# IN-00.net
KiCad netlist of a schematic drawn in EAGLE
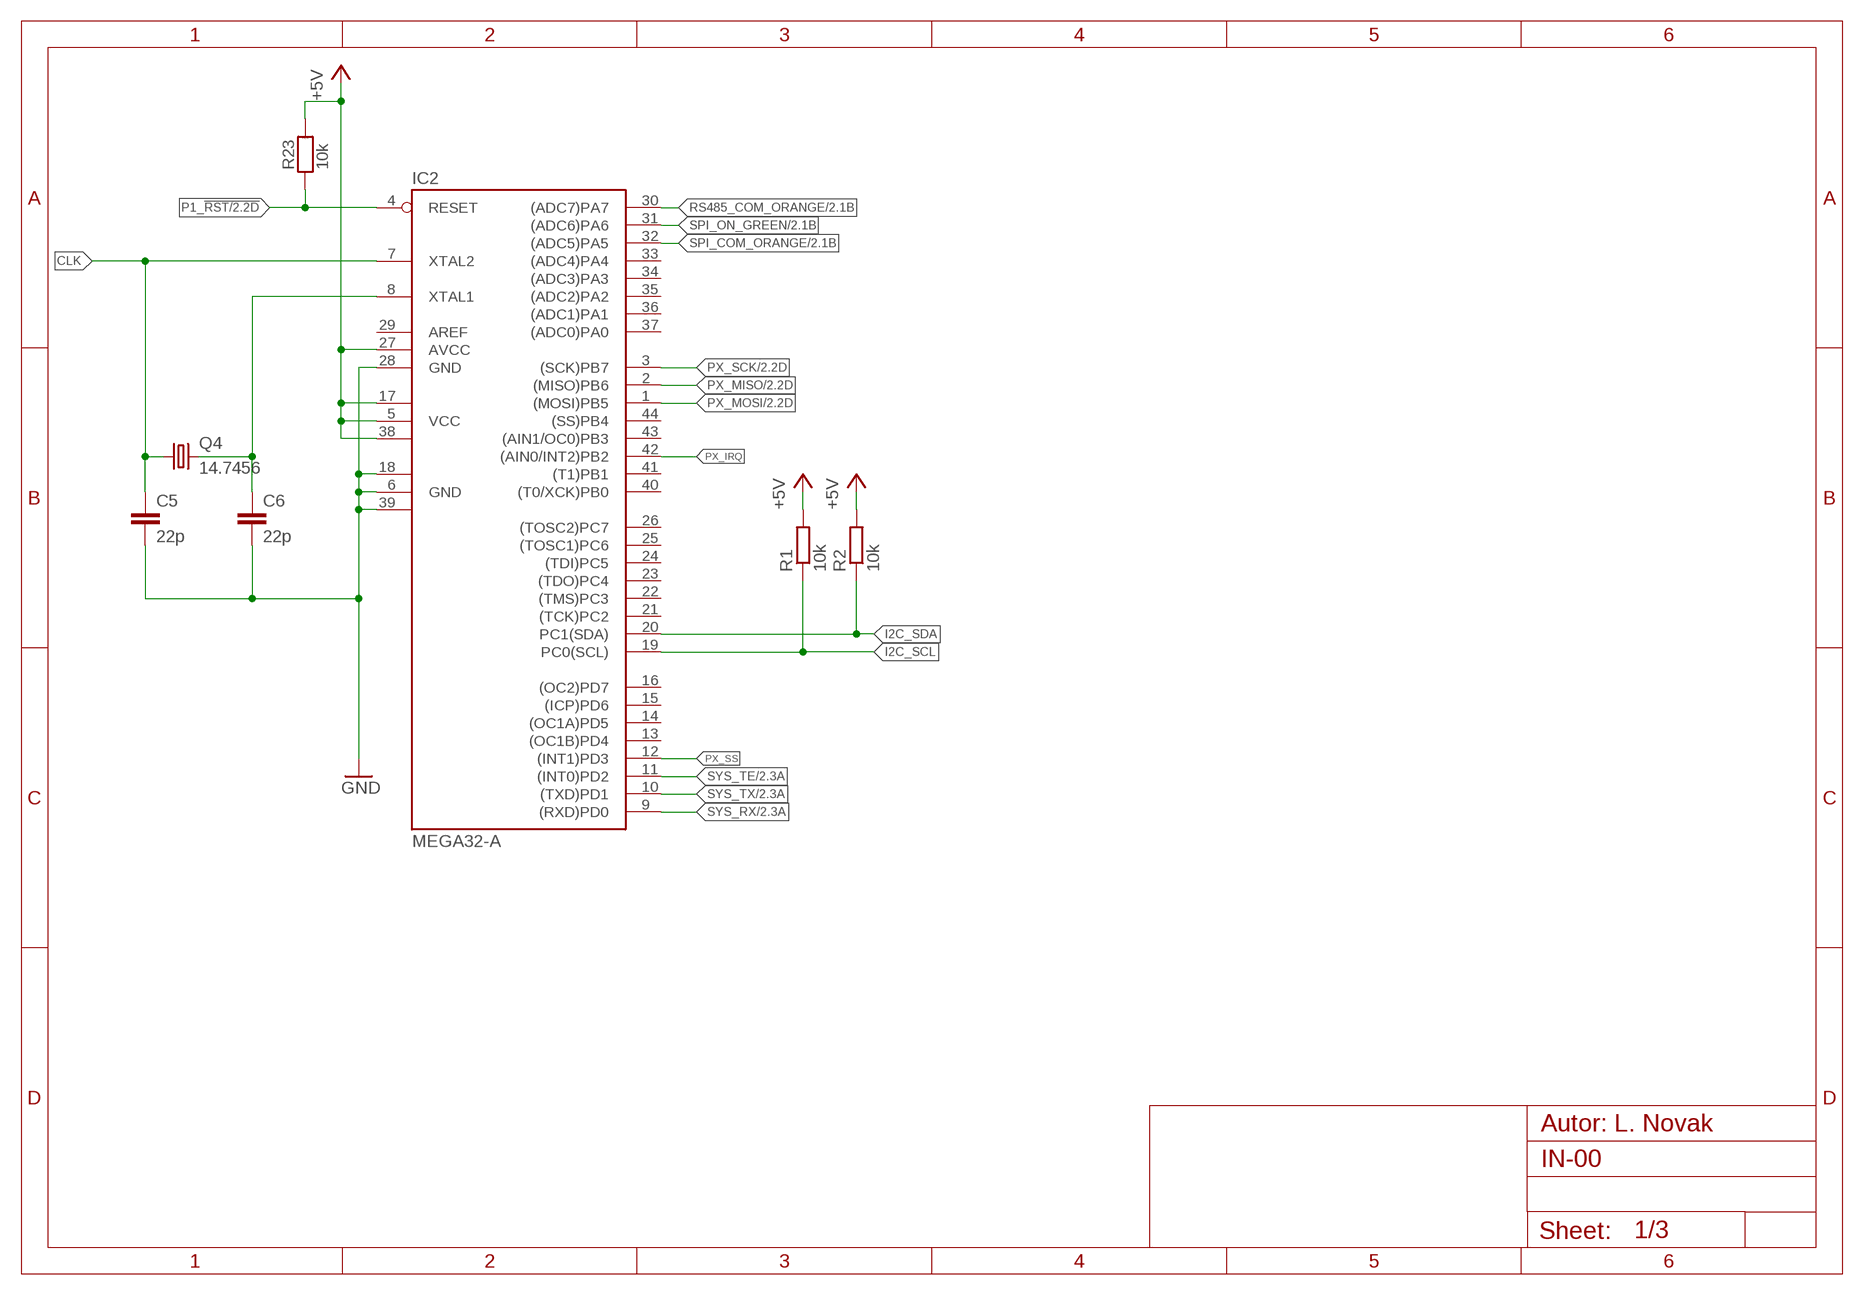
[diagram p0: schematic, sheet 1]
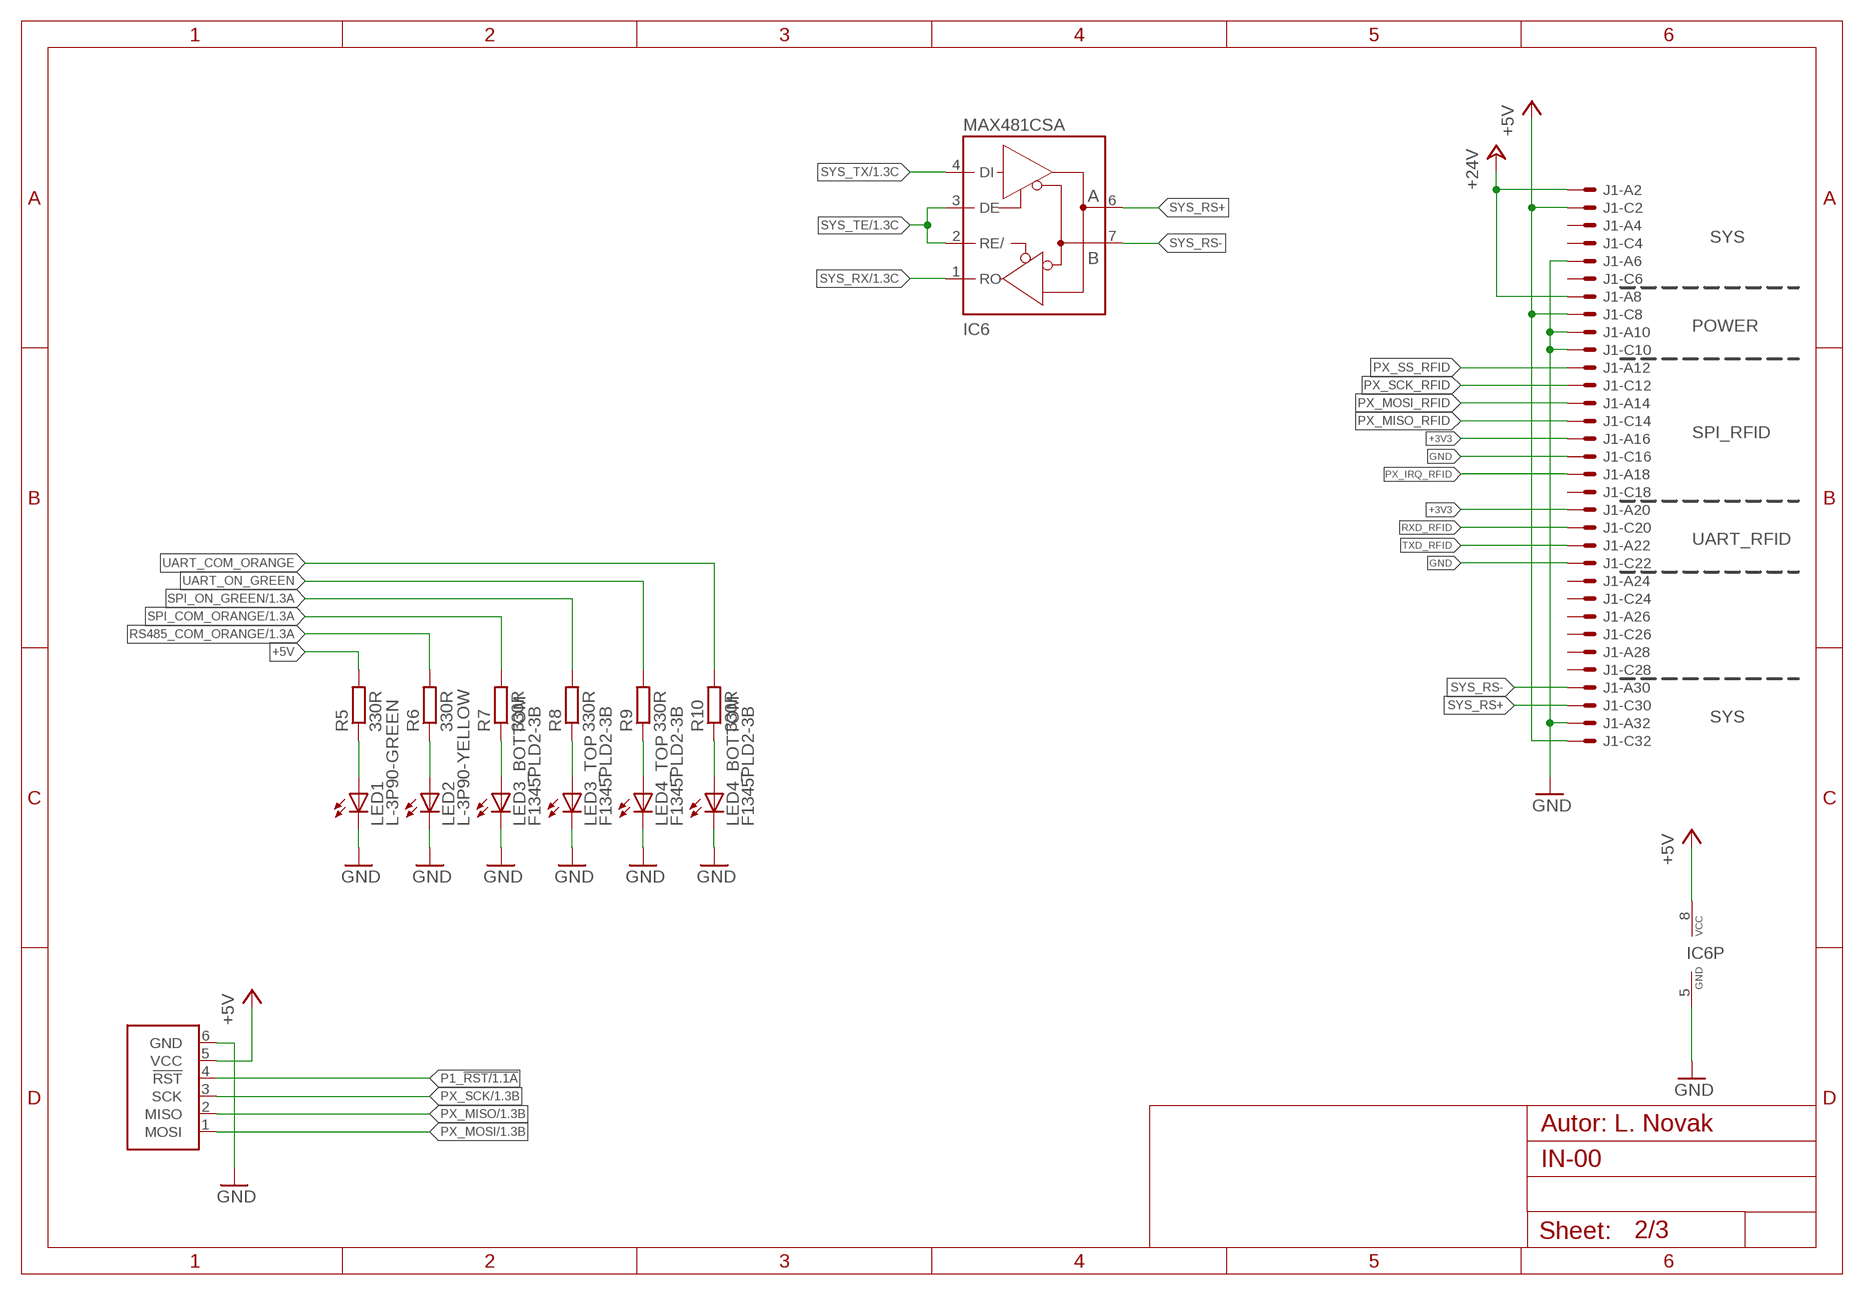
[diagram p1: schematic, sheet 2]
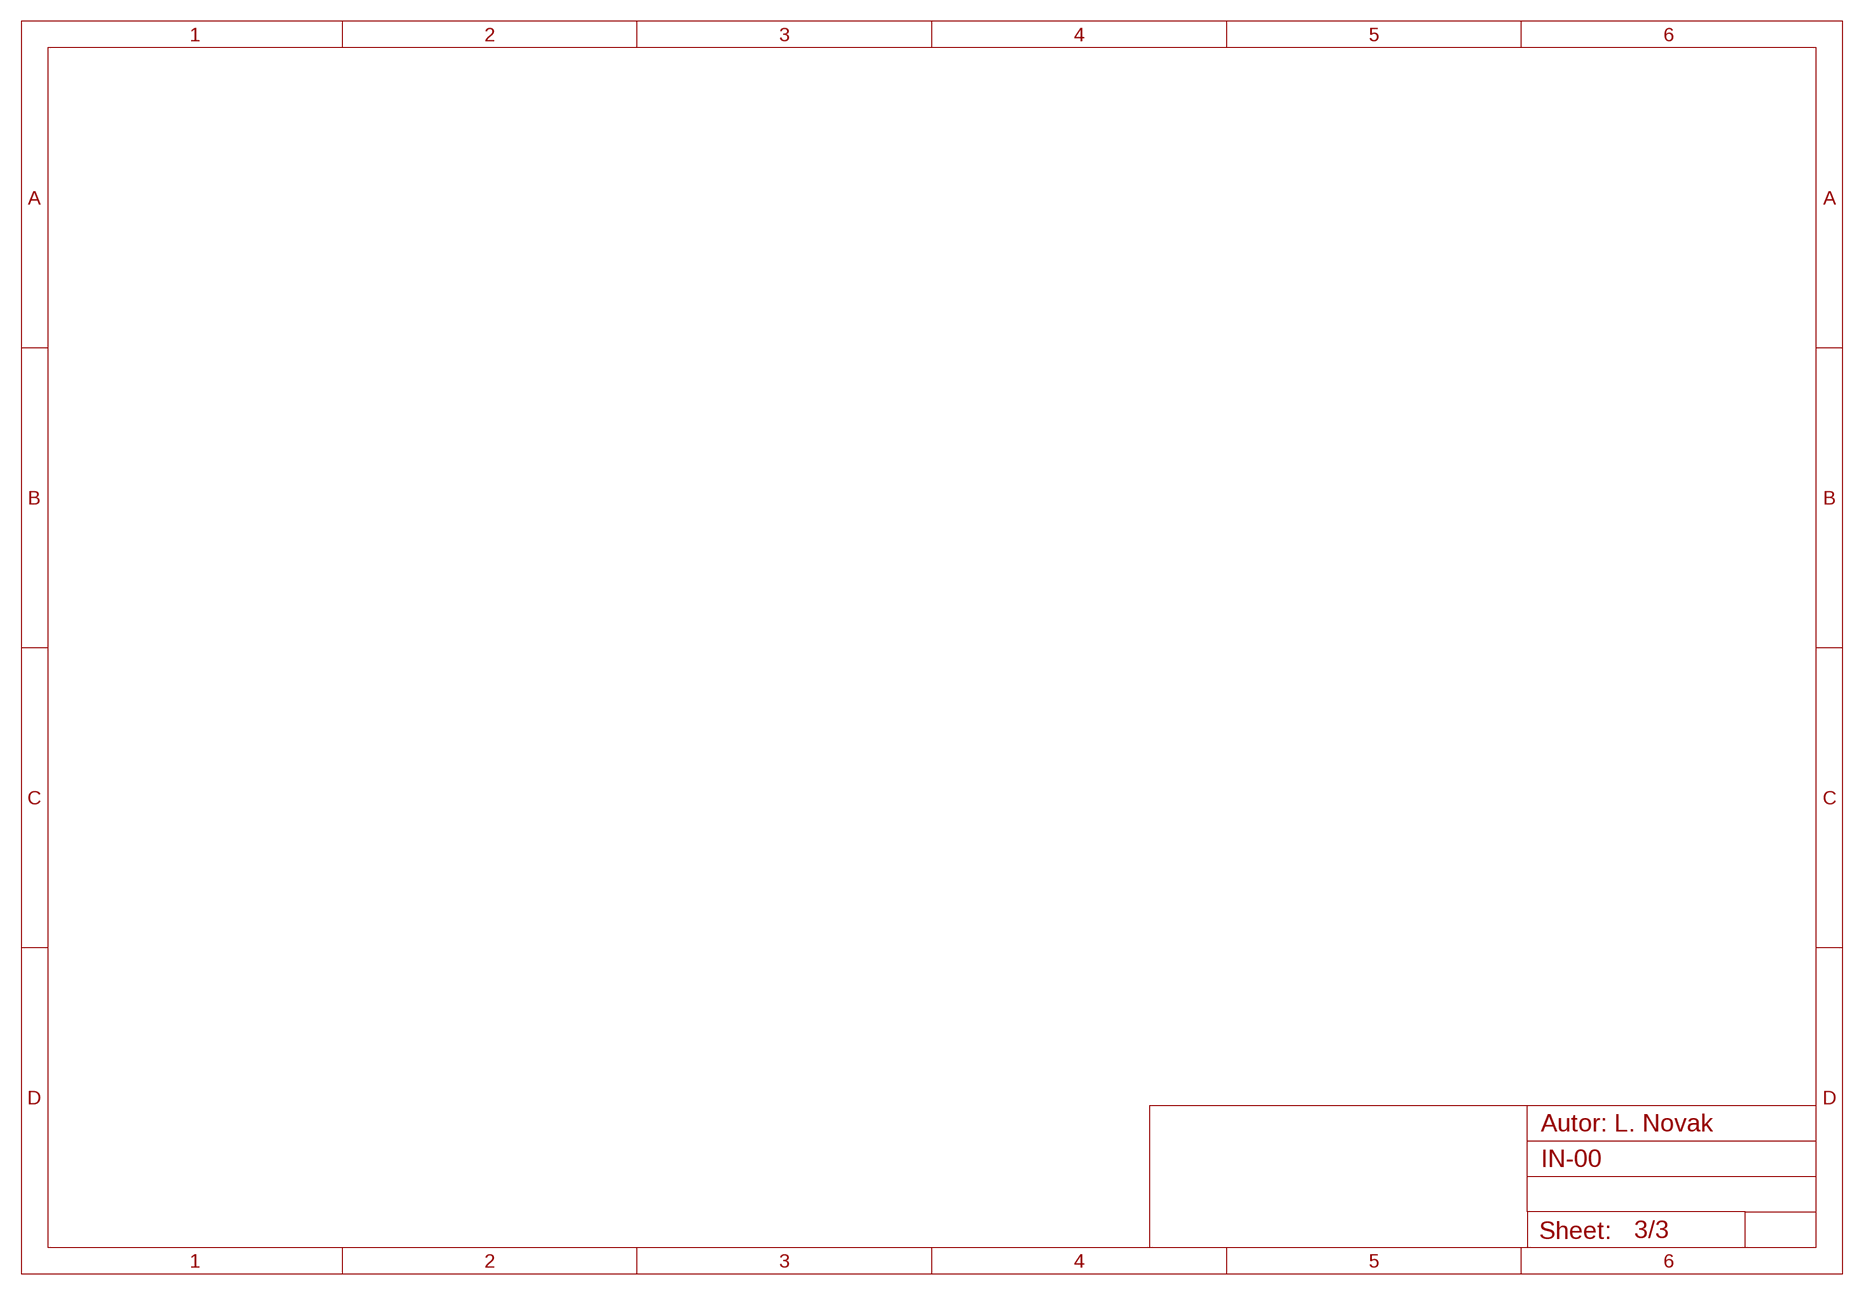
[diagram p2: schematic, sheet 3]

(export (version "E")
  (design (tool "Eeschema 10.0.6"))
  (components
    (comp (ref "IC6")
      (value "MAX481CSA")
      (footprint "eagle-import:SO08")
      (libsource (lib "eagle-import") (part "MAX481CSA"))
    )
    (comp (ref "J1")
      (value "VG32SP")
      (footprint "eagle-import:VG32P")
      (libsource (lib "eagle-import") (part "VG32SP"))
    )
    (comp (ref "LED1")
      (value "L-3P90-GREEN")
      (footprint "eagle-import:L-3P90")
      (libsource (lib "eagle-import") (part "L-3P90-GREEN"))
    )
    (comp (ref "LED2")
      (value "L-3P90-YELLOW")
      (footprint "eagle-import:L-3P90")
      (libsource (lib "eagle-import") (part "L-3P90-YELLOW"))
    )
    (comp (ref "LED3")
      (value "F1345PLD2-3B")
      (footprint "eagle-import:F1345PLD2-3B")
      (libsource (lib "eagle-import") (part "F1345PLD2-3B"))
    )
    (comp (ref "LED4")
      (value "F1345PLD2-3B")
      (footprint "eagle-import:F1345PLD2-3B")
      (libsource (lib "eagle-import") (part "F1345PLD2-3B"))
    )
    (comp (ref "R5")
      (value "330R")
      (footprint "eagle-import:R1206")
      (libsource (lib "eagle-import") (part "R-EU_R1206"))
    )
    (comp (ref "R6")
      (value "330R")
      (footprint "eagle-import:R1206")
      (libsource (lib "eagle-import") (part "R-EU_R1206"))
    )
    (comp (ref "R7")
      (value "330R")
      (footprint "eagle-import:R1206")
      (libsource (lib "eagle-import") (part "R-EU_R1206"))
    )
    (comp (ref "R8")
      (value "330R")
      (footprint "eagle-import:R1206")
      (libsource (lib "eagle-import") (part "R-EU_R1206"))
    )
    (comp (ref "R9")
      (value "330R")
      (footprint "eagle-import:R1206")
      (libsource (lib "eagle-import") (part "R-EU_R1206"))
    )
    (comp (ref "R10")
      (value "330R")
      (footprint "eagle-import:R1206")
      (libsource (lib "eagle-import") (part "R-EU_R1206"))
    )
    (comp (ref "U1")
      (value "ATPROG-V")
      (footprint "eagle-import:6410-06")
      (libsource (lib "eagle-import") (part "ATPROG-V"))
    )
    (comp (ref "C5")
      (value "22p")
      (footprint "eagle-import:C0805")
      (libsource (lib "eagle-import") (part "C-EUC0805"))
    )
    (comp (ref "C6")
      (value "22p")
      (footprint "eagle-import:C0805")
      (libsource (lib "eagle-import") (part "C-EUC0805"))
    )
    (comp (ref "IC2")
      (value "MEGA32-A")
      (footprint "eagle-import:TQFP44")
      (fields (field (name "MPN") "ATMEGA32-16AU"))
      (libsource (lib "eagle-import") (part "MEGA32-A"))
    )
    (comp (ref "Q4")
      (value "14.7456")
      (footprint "eagle-import:HC49U70")
      (libsource (lib "eagle-import") (part "XTAL"))
    )
    (comp (ref "R1")
      (value "10k")
      (footprint "eagle-import:R1206")
      (libsource (lib "eagle-import") (part "R-EU_R1206"))
    )
    (comp (ref "R2")
      (value "10k")
      (footprint "eagle-import:R1206")
      (libsource (lib "eagle-import") (part "R-EU_R1206"))
    )
    (comp (ref "R23")
      (value "10k")
      (footprint "eagle-import:1206")
      (libsource (lib "eagle-import") (part "R_1206"))
    )
  )
  (nets
    (net (code "1") (name "+3V3") (class "Default")
      (node (ref "J1") (pin "A16") (pinfunction "MS_A16") (pintype "passive"))
      (node (ref "J1") (pin "A20") (pinfunction "MS_A20") (pintype "passive"))
    )
    (net (code "2") (name "+5V") (class "Default")
      (node (ref "IC2") (pin "17") (pinfunction "VCC1_17") (pintype "power_in"))
      (node (ref "IC2") (pin "27") (pinfunction "AVCC_27") (pintype "power_in"))
      (node (ref "IC2") (pin "38") (pinfunction "VCC2_38") (pintype "power_in"))
      (node (ref "IC2") (pin "5") (pinfunction "VCC_5") (pintype "power_in"))
      (node (ref "IC6") (pin "8") (pinfunction "VCC_8") (pintype "power_in"))
      (node (ref "J1") (pin "C2") (pinfunction "MS_C2") (pintype "passive"))
      (node (ref "J1") (pin "C32") (pinfunction "MSV_C32") (pintype "passive"))
      (node (ref "J1") (pin "C8") (pinfunction "MS_C8") (pintype "passive"))
      (node (ref "R1") (pin "2") (pinfunction "2_2") (pintype "passive"))
      (node (ref "R2") (pin "2") (pinfunction "2_2") (pintype "passive"))
      (node (ref "R23") (pin "2") (pinfunction "2_2") (pintype "passive"))
      (node (ref "R5") (pin "2") (pinfunction "2_2") (pintype "passive"))
      (node (ref "U1") (pin "5") (pinfunction "VCC_5") (pintype "power_in"))
    )
    (net (code "3") (name "+24V") (class "Default")
      (node (ref "J1") (pin "A2") (pinfunction "MS_A2") (pintype "passive"))
      (node (ref "J1") (pin "A8") (pinfunction "MS_A8") (pintype "passive"))
    )
    (net (code "4") (name "CLK") (class "Default")
      (node (ref "C5") (pin "1") (pinfunction "1_1") (pintype "passive"))
      (node (ref "IC2") (pin "7") (pinfunction "XTAL2_7") (pintype "bidirectional"))
      (node (ref "Q4") (pin "1") (pinfunction "1_1") (pintype "passive"))
    )
    (net (code "5") (name "GND") (class "Default")
      (node (ref "C5") (pin "2") (pinfunction "2_2") (pintype "passive"))
      (node (ref "C6") (pin "2") (pinfunction "2_2") (pintype "passive"))
      (node (ref "IC2") (pin "18") (pinfunction "GND1_18") (pintype "power_in"))
      (node (ref "IC2") (pin "28") (pinfunction "GND_28") (pintype "power_in"))
      (node (ref "IC2") (pin "39") (pinfunction "GND2_39") (pintype "power_in"))
      (node (ref "IC2") (pin "6") (pinfunction "GND_6") (pintype "power_in"))
      (node (ref "IC6") (pin "5") (pinfunction "GND_5") (pintype "power_in"))
      (node (ref "J1") (pin "A10") (pinfunction "MS_A10") (pintype "passive"))
      (node (ref "J1") (pin "A32") (pinfunction "MS_A32") (pintype "passive"))
      (node (ref "J1") (pin "A6") (pinfunction "MS_A6") (pintype "passive"))
      (node (ref "J1") (pin "C10") (pinfunction "MS_C10") (pintype "passive"))
      (node (ref "J1") (pin "C16") (pinfunction "MS_C16") (pintype "passive"))
      (node (ref "J1") (pin "C22") (pinfunction "MS_C22") (pintype "passive"))
      (node (ref "LED1") (pin "K") (pinfunction "C_K") (pintype "passive"))
      (node (ref "LED2") (pin "K") (pinfunction "C_K") (pintype "passive"))
      (node (ref "LED3") (pin "1K") (pinfunction "C_1K") (pintype "passive"))
      (node (ref "LED3") (pin "2K") (pinfunction "C_2K") (pintype "passive"))
      (node (ref "LED4") (pin "1K") (pinfunction "C_1K") (pintype "passive"))
      (node (ref "LED4") (pin "2K") (pinfunction "C_2K") (pintype "passive"))
      (node (ref "U1") (pin "6") (pinfunction "GND_6") (pintype "power_in"))
    )
    (net (code "6") (name "I2C_SCL") (class "Default")
      (node (ref "IC2") (pin "19") (pinfunction "PC0(SCL)_19") (pintype "bidirectional"))
      (node (ref "R1") (pin "1") (pinfunction "1_1") (pintype "passive"))
    )
    (net (code "7") (name "I2C_SDA") (class "Default")
      (node (ref "IC2") (pin "20") (pinfunction "PC1(SDA)_20") (pintype "bidirectional"))
      (node (ref "R2") (pin "1") (pinfunction "1_1") (pintype "passive"))
    )
    (net (code "8") (name "Net-(IC2-XTAL1)") (class "Default")
      (node (ref "C6") (pin "1") (pinfunction "1_1") (pintype "passive"))
      (node (ref "IC2") (pin "8") (pinfunction "XTAL1_8") (pintype "bidirectional"))
      (node (ref "Q4") (pin "2") (pinfunction "2_2") (pintype "passive"))
    )
    (net (code "9") (name "Net-(LED1-PadA)") (class "Default")
      (node (ref "LED1") (pin "A") (pinfunction "A_A") (pintype "passive"))
      (node (ref "R5") (pin "1") (pinfunction "1_1") (pintype "passive"))
    )
    (net (code "10") (name "Net-(LED2-PadA)") (class "Default")
      (node (ref "LED2") (pin "A") (pinfunction "A_A") (pintype "passive"))
      (node (ref "R6") (pin "1") (pinfunction "1_1") (pintype "passive"))
    )
    (net (code "11") (name "Net-(LED3A-A)") (class "Default")
      (node (ref "LED3") (pin "1A") (pinfunction "A_1A") (pintype "passive"))
      (node (ref "R7") (pin "1") (pinfunction "1_1") (pintype "passive"))
    )
    (net (code "12") (name "Net-(LED3B-A)") (class "Default")
      (node (ref "LED3") (pin "2A") (pinfunction "A_2A") (pintype "passive"))
      (node (ref "R8") (pin "1") (pinfunction "1_1") (pintype "passive"))
    )
    (net (code "13") (name "Net-(LED4A-A)") (class "Default")
      (node (ref "LED4") (pin "1A") (pinfunction "A_1A") (pintype "passive"))
      (node (ref "R10") (pin "1") (pinfunction "1_1") (pintype "passive"))
    )
    (net (code "14") (name "Net-(LED4B-A)") (class "Default")
      (node (ref "LED4") (pin "2A") (pinfunction "A_2A") (pintype "passive"))
      (node (ref "R9") (pin "1") (pinfunction "1_1") (pintype "passive"))
    )
    (net (code "15") (name "P1_~{RST}") (class "Default")
      (node (ref "IC2") (pin "4") (pinfunction "RESET_4") (pintype "input"))
      (node (ref "R23") (pin "1") (pinfunction "1_1") (pintype "passive"))
      (node (ref "U1") (pin "4") (pinfunction "~{RST}_4") (pintype "input"))
    )
    (net (code "16") (name "PX_IRQ") (class "Default")
      (node (ref "IC2") (pin "42") (pinfunction "(AIN0/INT2)PB2_42") (pintype "bidirectional"))
    )
    (net (code "17") (name "PX_IRQ_RFID") (class "Default")
      (node (ref "J1") (pin "A18") (pinfunction "MS_A18") (pintype "passive"))
    )
    (net (code "18") (name "PX_MISO") (class "Default")
      (node (ref "IC2") (pin "2") (pinfunction "(MISO)PB6_2") (pintype "bidirectional"))
      (node (ref "U1") (pin "2") (pinfunction "MISO_2") (pintype "input"))
    )
    (net (code "19") (name "PX_MISO_RFID") (class "Default")
      (node (ref "J1") (pin "C14") (pinfunction "MS_C14") (pintype "passive"))
    )
    (net (code "20") (name "PX_MOSI") (class "Default")
      (node (ref "IC2") (pin "1") (pinfunction "(MOSI)PB5_1") (pintype "bidirectional"))
      (node (ref "U1") (pin "1") (pinfunction "MOSI_1") (pintype "output"))
    )
    (net (code "21") (name "PX_MOSI_RFID") (class "Default")
      (node (ref "J1") (pin "A14") (pinfunction "MS_A14") (pintype "passive"))
    )
    (net (code "22") (name "PX_SCK") (class "Default")
      (node (ref "IC2") (pin "3") (pinfunction "(SCK)PB7_3") (pintype "bidirectional"))
      (node (ref "U1") (pin "3") (pinfunction "SCK_3") (pintype "input"))
    )
    (net (code "23") (name "PX_SCK_RFID") (class "Default")
      (node (ref "J1") (pin "C12") (pinfunction "MS_C12") (pintype "passive"))
    )
    (net (code "24") (name "PX_SS") (class "Default")
      (node (ref "IC2") (pin "12") (pinfunction "(INT1)PD3_12") (pintype "bidirectional"))
    )
    (net (code "25") (name "PX_SS_RFID") (class "Default")
      (node (ref "J1") (pin "A12") (pinfunction "MS_A12") (pintype "passive"))
    )
    (net (code "26") (name "RS485_COM_ORANGE") (class "Default")
      (node (ref "IC2") (pin "30") (pinfunction "(ADC7)PA7_30") (pintype "bidirectional"))
      (node (ref "R6") (pin "2") (pinfunction "2_2") (pintype "passive"))
    )
    (net (code "27") (name "RXD_RFID") (class "Default")
      (node (ref "J1") (pin "C20") (pinfunction "MS_C20") (pintype "passive"))
    )
    (net (code "28") (name "SPI_COM_ORANGE") (class "Default")
      (node (ref "IC2") (pin "32") (pinfunction "(ADC5)PA5_32") (pintype "bidirectional"))
      (node (ref "R7") (pin "2") (pinfunction "2_2") (pintype "passive"))
    )
    (net (code "29") (name "SPI_ON_GREEN") (class "Default")
      (node (ref "IC2") (pin "31") (pinfunction "(ADC6)PA6_31") (pintype "bidirectional"))
      (node (ref "R8") (pin "2") (pinfunction "2_2") (pintype "passive"))
    )
    (net (code "30") (name "SYS_RS+") (class "Default")
      (node (ref "IC6") (pin "6") (pinfunction "A_6") (pintype "passive"))
      (node (ref "J1") (pin "C30") (pinfunction "MS_C30") (pintype "passive"))
    )
    (net (code "31") (name "SYS_RS-") (class "Default")
      (node (ref "IC6") (pin "7") (pinfunction "B_7") (pintype "passive"))
      (node (ref "J1") (pin "A30") (pinfunction "MS_A30") (pintype "passive"))
    )
    (net (code "32") (name "SYS_RX") (class "Default")
      (node (ref "IC2") (pin "9") (pinfunction "(RXD)PD0_9") (pintype "bidirectional"))
      (node (ref "IC6") (pin "1") (pinfunction "RO_1") (pintype "output"))
    )
    (net (code "33") (name "SYS_TE") (class "Default")
      (node (ref "IC2") (pin "11") (pinfunction "(INT0)PD2_11") (pintype "bidirectional"))
      (node (ref "IC6") (pin "2") (pinfunction "RE/_2") (pintype "input"))
      (node (ref "IC6") (pin "3") (pinfunction "DE_3") (pintype "input"))
    )
    (net (code "34") (name "SYS_TX") (class "Default")
      (node (ref "IC2") (pin "10") (pinfunction "(TXD)PD1_10") (pintype "bidirectional"))
      (node (ref "IC6") (pin "4") (pinfunction "DI_4") (pintype "input"))
    )
    (net (code "35") (name "TXD_RFID") (class "Default")
      (node (ref "J1") (pin "A22") (pinfunction "MS_A22") (pintype "passive"))
    )
    (net (code "36") (name "UART_COM_ORANGE") (class "Default")
      (node (ref "R10") (pin "2") (pinfunction "2_2") (pintype "passive"))
    )
    (net (code "37") (name "UART_ON_GREEN") (class "Default")
      (node (ref "R9") (pin "2") (pinfunction "2_2") (pintype "passive"))
    )
    (net (code "38") (name "unconnected-(IC2-(ADC0)PA0-Pad37)") (class "Default")
      (node (ref "IC2") (pin "37") (pinfunction "(ADC0)PA0_37") (pintype "bidirectional"))
    )
    (net (code "39") (name "unconnected-(IC2-(ADC1)PA1-Pad36)") (class "Default")
      (node (ref "IC2") (pin "36") (pinfunction "(ADC1)PA1_36") (pintype "bidirectional"))
    )
    (net (code "40") (name "unconnected-(IC2-(ADC2)PA2-Pad35)") (class "Default")
      (node (ref "IC2") (pin "35") (pinfunction "(ADC2)PA2_35") (pintype "bidirectional"))
    )
    (net (code "41") (name "unconnected-(IC2-(ADC3)PA3-Pad34)") (class "Default")
      (node (ref "IC2") (pin "34") (pinfunction "(ADC3)PA3_34") (pintype "bidirectional"))
    )
    (net (code "42") (name "unconnected-(IC2-(ADC4)PA4-Pad33)") (class "Default")
      (node (ref "IC2") (pin "33") (pinfunction "(ADC4)PA4_33") (pintype "bidirectional"))
    )
    (net (code "43") (name "unconnected-(IC2-(AIN1{slash}OC0)PB3-Pad43)") (class "Default")
      (node (ref "IC2") (pin "43") (pinfunction "(AIN1/OC0)PB3_43") (pintype "bidirectional"))
    )
    (net (code "44") (name "unconnected-(IC2-(ICP)PD6-Pad15)") (class "Default")
      (node (ref "IC2") (pin "15") (pinfunction "(ICP)PD6_15") (pintype "bidirectional"))
    )
    (net (code "45") (name "unconnected-(IC2-(OC1A)PD5-Pad14)") (class "Default")
      (node (ref "IC2") (pin "14") (pinfunction "(OC1A)PD5_14") (pintype "bidirectional"))
    )
    (net (code "46") (name "unconnected-(IC2-(OC1B)PD4-Pad13)") (class "Default")
      (node (ref "IC2") (pin "13") (pinfunction "(OC1B)PD4_13") (pintype "bidirectional"))
    )
    (net (code "47") (name "unconnected-(IC2-(OC2)PD7-Pad16)") (class "Default")
      (node (ref "IC2") (pin "16") (pinfunction "(OC2)PD7_16") (pintype "bidirectional"))
    )
    (net (code "48") (name "unconnected-(IC2-(SS)PB4-Pad44)") (class "Default")
      (node (ref "IC2") (pin "44") (pinfunction "(SS)PB4_44") (pintype "bidirectional"))
    )
    (net (code "49") (name "unconnected-(IC2-(T0{slash}XCK)PB0-Pad40)") (class "Default")
      (node (ref "IC2") (pin "40") (pinfunction "(T0/XCK)PB0_40") (pintype "bidirectional"))
    )
    (net (code "50") (name "unconnected-(IC2-(T1)PB1-Pad41)") (class "Default")
      (node (ref "IC2") (pin "41") (pinfunction "(T1)PB1_41") (pintype "bidirectional"))
    )
    (net (code "51") (name "unconnected-(IC2-(TCK)PC2-Pad21)") (class "Default")
      (node (ref "IC2") (pin "21") (pinfunction "(TCK)PC2_21") (pintype "bidirectional"))
    )
    (net (code "52") (name "unconnected-(IC2-(TDI)PC5-Pad24)") (class "Default")
      (node (ref "IC2") (pin "24") (pinfunction "(TDI)PC5_24") (pintype "bidirectional"))
    )
    (net (code "53") (name "unconnected-(IC2-(TDO)PC4-Pad23)") (class "Default")
      (node (ref "IC2") (pin "23") (pinfunction "(TDO)PC4_23") (pintype "bidirectional"))
    )
    (net (code "54") (name "unconnected-(IC2-(TMS)PC3-Pad22)") (class "Default")
      (node (ref "IC2") (pin "22") (pinfunction "(TMS)PC3_22") (pintype "bidirectional"))
    )
    (net (code "55") (name "unconnected-(IC2-(TOSC1)PC6-Pad25)") (class "Default")
      (node (ref "IC2") (pin "25") (pinfunction "(TOSC1)PC6_25") (pintype "bidirectional"))
    )
    (net (code "56") (name "unconnected-(IC2-(TOSC2)PC7-Pad26)") (class "Default")
      (node (ref "IC2") (pin "26") (pinfunction "(TOSC2)PC7_26") (pintype "bidirectional"))
    )
    (net (code "57") (name "unconnected-(IC2-AREF-Pad29)") (class "Default")
      (node (ref "IC2") (pin "29") (pinfunction "AREF_29") (pintype "passive"))
    )
    (net (code "58") (name "unconnected-(J1AA-MS-PadC28)") (class "Default")
      (node (ref "J1") (pin "C28") (pinfunction "MS_C28") (pintype "passive"))
    )
    (net (code "59") (name "unconnected-(J1AD-MS-PadC4)") (class "Default")
      (node (ref "J1") (pin "C4") (pinfunction "MS_C4") (pintype "passive"))
    )
    (net (code "60") (name "unconnected-(J1AE-MS-PadC6)") (class "Default")
      (node (ref "J1") (pin "C6") (pinfunction "MS_C6") (pintype "passive"))
    )
    (net (code "61") (name "unconnected-(J1I-MS-PadA24)") (class "Default")
      (node (ref "J1") (pin "A24") (pinfunction "MS_A24") (pintype "passive"))
    )
    (net (code "62") (name "unconnected-(J1J-MS-PadA26)") (class "Default")
      (node (ref "J1") (pin "A26") (pinfunction "MS_A26") (pintype "passive"))
    )
    (net (code "63") (name "unconnected-(J1K-MS-PadA28)") (class "Default")
      (node (ref "J1") (pin "A28") (pinfunction "MS_A28") (pintype "passive"))
    )
    (net (code "64") (name "unconnected-(J1N-MS-PadA4)") (class "Default")
      (node (ref "J1") (pin "A4") (pinfunction "MS_A4") (pintype "passive"))
    )
    (net (code "65") (name "unconnected-(J1U-MS-PadC18)") (class "Default")
      (node (ref "J1") (pin "C18") (pinfunction "MS_C18") (pintype "passive"))
    )
    (net (code "66") (name "unconnected-(J1Y-MS-PadC24)") (class "Default")
      (node (ref "J1") (pin "C24") (pinfunction "MS_C24") (pintype "passive"))
    )
    (net (code "67") (name "unconnected-(J1Z-MS-PadC26)") (class "Default")
      (node (ref "J1") (pin "C26") (pinfunction "MS_C26") (pintype "passive"))
    )
  )
)
